# ramanSpectrometer_electronic_controlBoar.net
KiCad netlist of a schematic drawn in EAGLE
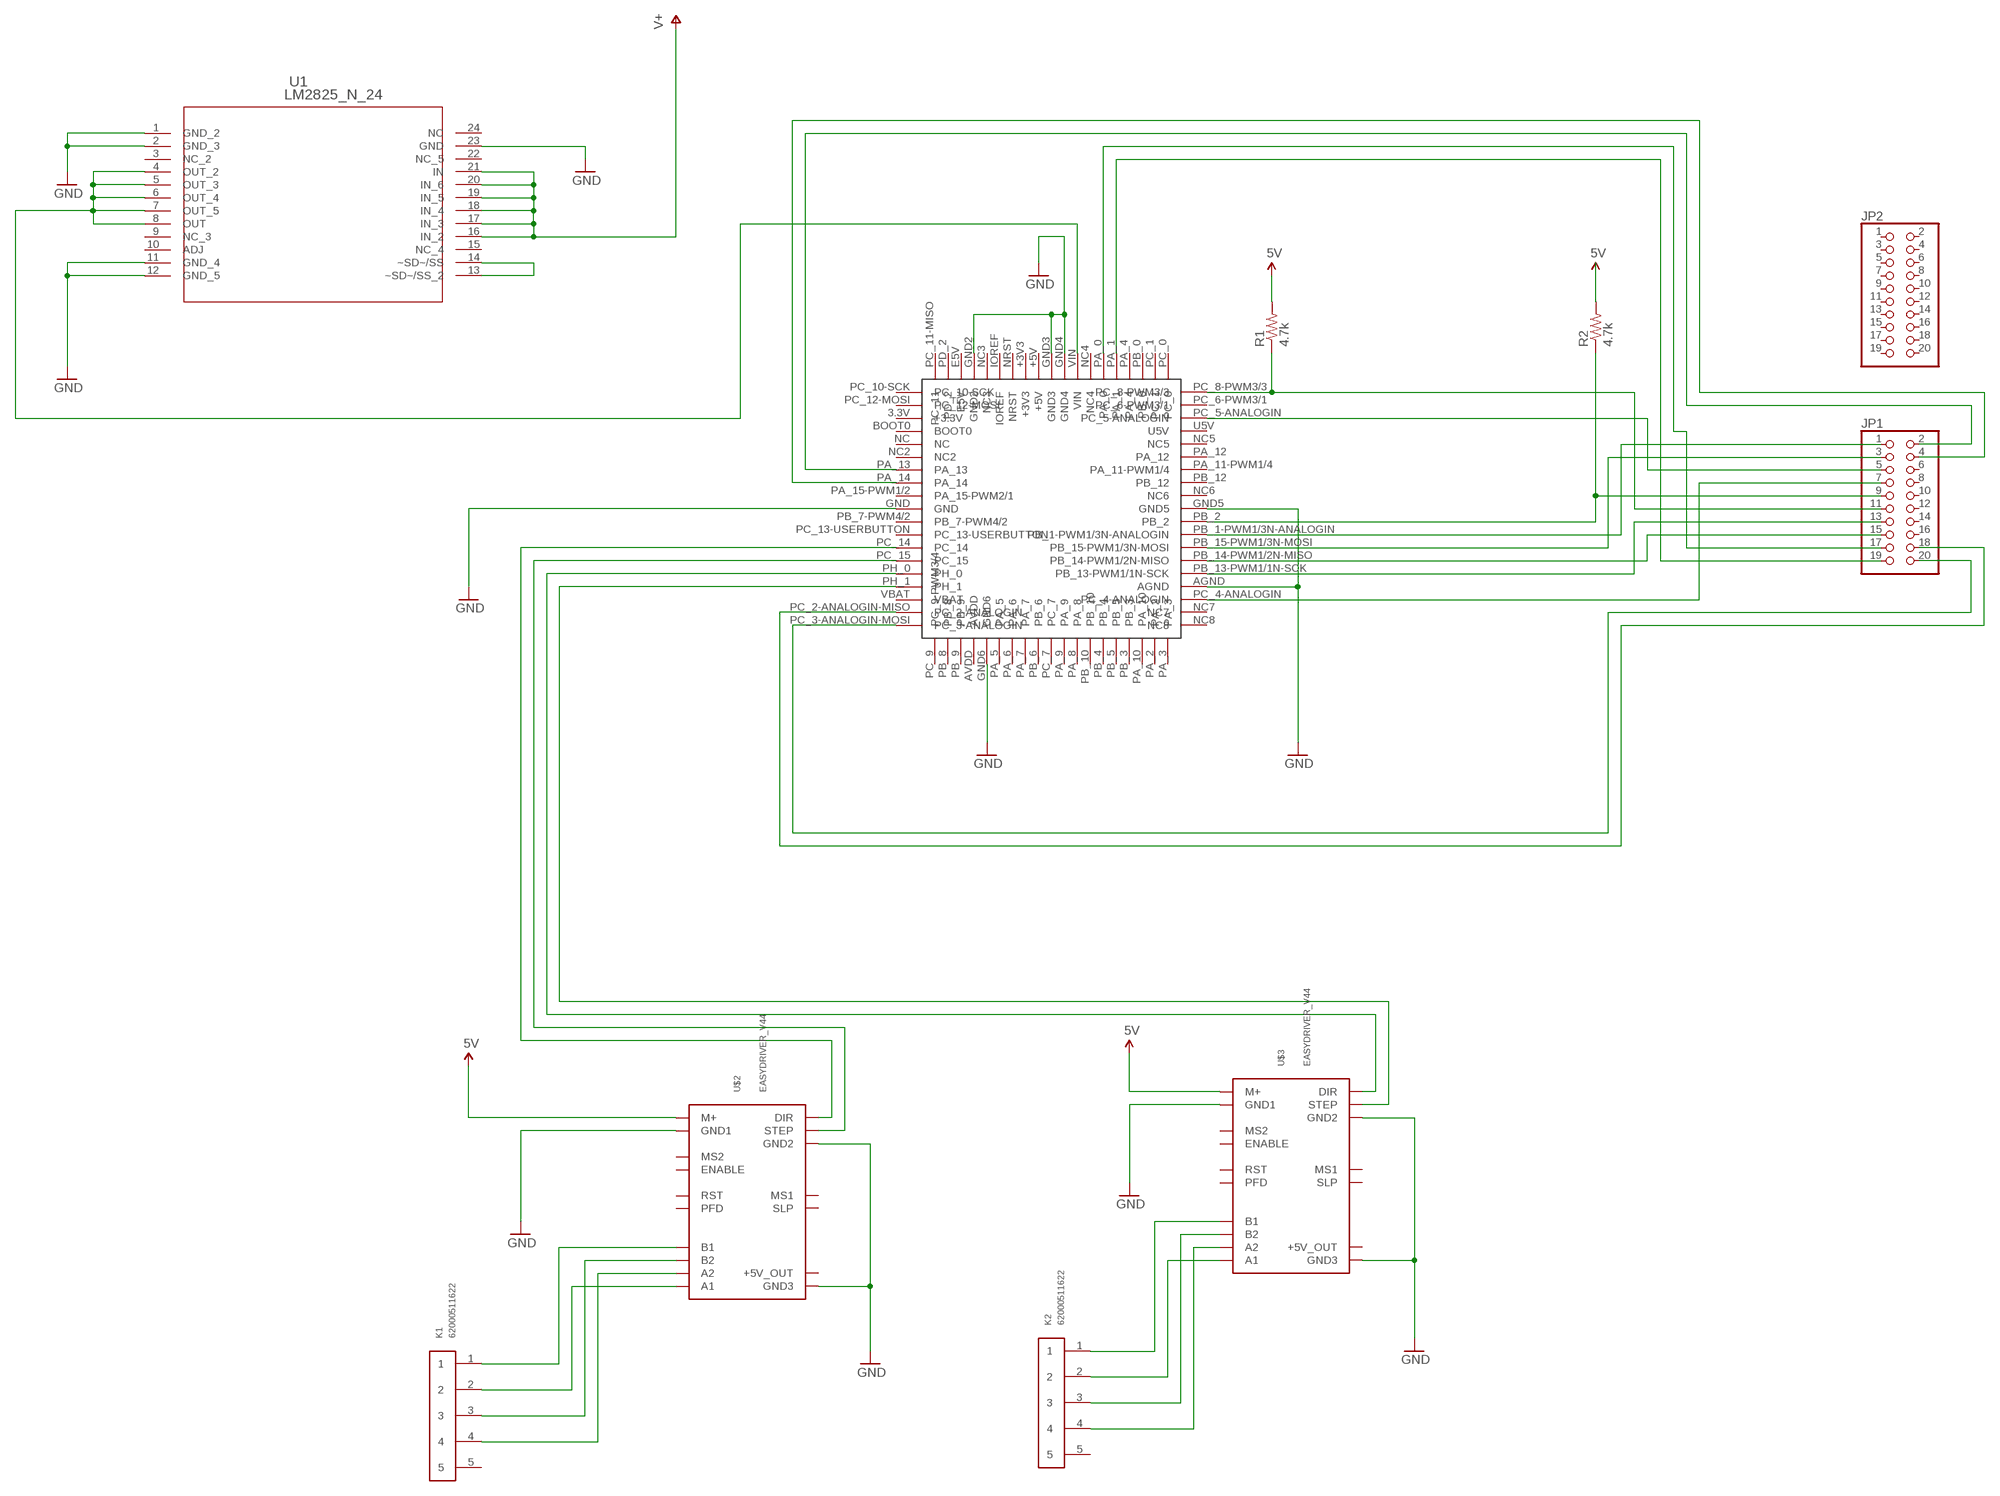
[diagram p0: schematic, sheet 1]

(export (version "E")
  (design (tool "Eeschema 10.0.6"))
  (components
    (comp (ref "JP1")
      (value "PINHD-2X10")
      (footprint "eagle-import:2X10")
      (libsource (lib "eagle-import") (part "PINHD-2X10"))
    )
    (comp (ref "JP2")
      (value "PINHD-2X10")
      (footprint "eagle-import:2X10")
      (libsource (lib "eagle-import") (part "PINHD-2X10"))
    )
    (comp (ref "K1")
      (value "62000511622")
      (footprint "eagle-import:62000511622")
      (libsource (lib "eagle-import") (part "62000511622"))
    )
    (comp (ref "K2")
      (value "62000511622")
      (footprint "eagle-import:62000511622")
      (libsource (lib "eagle-import") (part "62000511622"))
    )
    (comp (ref "R1")
      (value "4.7k")
      (footprint "eagle-import:AXIAL-0.3-KIT")
      (libsource (lib "eagle-import") (part "RESISTORKIT"))
    )
    (comp (ref "R2")
      (value "4.7k")
      (footprint "eagle-import:AXIAL-0.3-KIT")
      (libsource (lib "eagle-import") (part "RESISTORKIT"))
    )
    (comp (ref "U$1")
      (value "STNUCLEOF401RE")
      (footprint "eagle-import:F401-RE")
      (libsource (lib "eagle-import") (part "STNUCLEOF401RE"))
    )
    (comp (ref "U$2")
      (value "EASYDRIVER_V44")
      (footprint "eagle-import:EASYDRIVER_V44")
      (libsource (lib "eagle-import") (part "EASYDRIVER_V44"))
    )
    (comp (ref "U$3")
      (value "EASYDRIVER_V44")
      (footprint "eagle-import:EASYDRIVER_V44")
      (libsource (lib "eagle-import") (part "EASYDRIVER_V44"))
    )
    (comp (ref "U1")
      (value "LM2825_N_24")
      (footprint "eagle-import:NA24F")
      (fields (field (name "PARTNUMBER") "LM2825HN-ADJ"))
      (libsource (lib "eagle-import") (part "LM2825_N_24"))
    )
  )
  (nets
    (net (code "1") (name "/+3.3V") (class "Default")
      (node (ref "U$1") (pin "3.3V") (pinfunction "+3.3V_3.3V") (pintype "power_in"))
    )
    (net (code "2") (name "/AVDD") (class "Default")
      (node (ref "U$1") (pin "AVDD") (pinfunction "AVDD_AVDD") (pintype "power_in"))
    )
    (net (code "3") (name "/E5V") (class "Default")
      (node (ref "U$1") (pin "E5V") (pinfunction "E5V_E5V") (pintype "power_in"))
    )
    (net (code "4") (name "/NC6") (class "Default")
      (node (ref "U$1") (pin "NC6") (pinfunction "NC6_NC6") (pintype "power_in"))
    )
    (net (code "5") (name "/VBAT") (class "Default")
      (node (ref "U$1") (pin "VBAT") (pinfunction "VBAT_VBAT") (pintype "power_in"))
    )
    (net (code "6") (name "5V") (class "Default")
      (node (ref "R1") (pin "P$2") (pinfunction "2_P$2") (pintype "passive"))
      (node (ref "R2") (pin "P$2") (pinfunction "2_P$2") (pintype "passive"))
      (node (ref "U$2") (pin "M+") (pinfunction "M+_M+") (pintype "bidirectional"))
      (node (ref "U$3") (pin "M+") (pinfunction "M+_M+") (pintype "bidirectional"))
    )
    (net (code "7") (name "GND") (class "Default")
      (node (ref "U$1") (pin "AGND") (pinfunction "AGND_AGND") (pintype "power_in"))
      (node (ref "U$1") (pin "GND") (pinfunction "GND_GND") (pintype "power_in"))
      (node (ref "U$1") (pin "GND2") (pinfunction "GND2_GND2") (pintype "power_in"))
      (node (ref "U$1") (pin "GND3") (pinfunction "GND3_GND3") (pintype "bidirectional"))
      (node (ref "U$1") (pin "GND4") (pinfunction "GND4_GND4") (pintype "bidirectional"))
      (node (ref "U$1") (pin "GND5") (pinfunction "GND5_GND5") (pintype "bidirectional"))
      (node (ref "U$1") (pin "GND6") (pinfunction "GND6_GND6") (pintype "bidirectional"))
      (node (ref "U$2") (pin "GND1") (pinfunction "GND1_GND1") (pintype "bidirectional"))
      (node (ref "U$2") (pin "GND2") (pinfunction "GND2_GND2") (pintype "bidirectional"))
      (node (ref "U$2") (pin "GND3") (pinfunction "GND3_GND3") (pintype "bidirectional"))
      (node (ref "U$3") (pin "GND1") (pinfunction "GND1_GND1") (pintype "bidirectional"))
      (node (ref "U$3") (pin "GND2") (pinfunction "GND2_GND2") (pintype "bidirectional"))
      (node (ref "U$3") (pin "GND3") (pinfunction "GND3_GND3") (pintype "bidirectional"))
      (node (ref "U1") (pin "1") (pinfunction "GND_2_1") (pintype "passive"))
      (node (ref "U1") (pin "11") (pinfunction "GND_4_11") (pintype "passive"))
      (node (ref "U1") (pin "12") (pinfunction "GND_5_12") (pintype "passive"))
      (node (ref "U1") (pin "2") (pinfunction "GND_3_2") (pintype "passive"))
      (node (ref "U1") (pin "23") (pinfunction "GND_23") (pintype "passive"))
    )
    (net (code "8") (name "Net-(JP1-Pad1)") (class "Default")
      (node (ref "JP1") (pin "1") (pinfunction "1_1") (pintype "passive"))
      (node (ref "U$1") (pin "PB_1-PWM1/3N-ANALOGIN") (pinfunction "PB_1-PWM1/3N-ANALOGIN_PB_1-PWM1/3N-ANALOGIN") (pintype "bidirectional"))
    )
    (net (code "9") (name "Net-(JP1-Pad2)") (class "Default")
      (node (ref "JP1") (pin "2") (pinfunction "2_2") (pintype "passive"))
      (node (ref "U$1") (pin "PA_13") (pinfunction "PA_13_PA_13") (pintype "bidirectional"))
    )
    (net (code "10") (name "Net-(JP1-Pad3)") (class "Default")
      (node (ref "JP1") (pin "3") (pinfunction "3_3") (pintype "passive"))
      (node (ref "U$1") (pin "PB_15-PWM1/3N-MOSI") (pinfunction "PB_15-PWM1/3N-MOSI_PB_15-PWM1/3N-MOSI") (pintype "bidirectional"))
    )
    (net (code "11") (name "Net-(JP1-Pad4)") (class "Default")
      (node (ref "JP1") (pin "4") (pinfunction "4_4") (pintype "passive"))
      (node (ref "U$1") (pin "PA_14") (pinfunction "PA_14_PA_14") (pintype "bidirectional"))
    )
    (net (code "12") (name "Net-(JP1-Pad5)") (class "Default")
      (node (ref "JP1") (pin "5") (pinfunction "5_5") (pintype "passive"))
      (node (ref "U$1") (pin "PC_5-ANALOGIN") (pinfunction "PC_5-ANALOGIN_PC_5-ANALOGIN") (pintype "bidirectional"))
    )
    (net (code "13") (name "Net-(JP1-Pad7)") (class "Default")
      (node (ref "JP1") (pin "7") (pinfunction "7_7") (pintype "passive"))
      (node (ref "U$1") (pin "PC_4-ANALOGIN") (pinfunction "PC_4-ANALOGIN_PC_4-ANALOGIN") (pintype "bidirectional"))
    )
    (net (code "14") (name "Net-(JP1-Pad13)") (class "Default")
      (node (ref "JP1") (pin "13") (pinfunction "13_13") (pintype "passive"))
      (node (ref "U$1") (pin "PB_13-PWM1/1N-SCK") (pinfunction "PB_13-PWM1/1N-SCK_PB_13-PWM1/1N-SCK") (pintype "bidirectional"))
    )
    (net (code "15") (name "Net-(JP1-Pad15)") (class "Default")
      (node (ref "JP1") (pin "15") (pinfunction "15_15") (pintype "passive"))
      (node (ref "U$1") (pin "PB_14-PWM1/2N-MISO") (pinfunction "PB_14-PWM1/2N-MISO_PB_14-PWM1/2N-MISO") (pintype "bidirectional"))
    )
    (net (code "16") (name "Net-(JP1-Pad17)") (class "Default")
      (node (ref "JP1") (pin "17") (pinfunction "17_17") (pintype "passive"))
      (node (ref "U$1") (pin "PA_0") (pinfunction "PA_0_PA_0") (pintype "bidirectional"))
    )
    (net (code "17") (name "Net-(JP1-Pad19)") (class "Default")
      (node (ref "JP1") (pin "19") (pinfunction "19_19") (pintype "passive"))
      (node (ref "U$1") (pin "PA_1") (pinfunction "PA_1_PA_1") (pintype "bidirectional"))
    )
    (net (code "18") (name "Net-(K1-Pad1)") (class "Default")
      (node (ref "K1") (pin "1") (pinfunction "1_1") (pintype "bidirectional"))
      (node (ref "U$2") (pin "B1") (pinfunction "B1_B1") (pintype "bidirectional"))
    )
    (net (code "19") (name "Net-(K1-Pad2)") (class "Default")
      (node (ref "K1") (pin "2") (pinfunction "2_2") (pintype "bidirectional"))
      (node (ref "U$2") (pin "A1") (pinfunction "A1_A1") (pintype "bidirectional"))
    )
    (net (code "20") (name "Net-(K1-Pad3)") (class "Default")
      (node (ref "K1") (pin "3") (pinfunction "3_3") (pintype "bidirectional"))
      (node (ref "U$2") (pin "B2") (pinfunction "B2_B2") (pintype "bidirectional"))
    )
    (net (code "21") (name "Net-(K1-Pad4)") (class "Default")
      (node (ref "K1") (pin "4") (pinfunction "4_4") (pintype "bidirectional"))
      (node (ref "U$2") (pin "A2") (pinfunction "A2_A2") (pintype "bidirectional"))
    )
    (net (code "22") (name "Net-(K2-Pad1)") (class "Default")
      (node (ref "K2") (pin "1") (pinfunction "1_1") (pintype "bidirectional"))
      (node (ref "U$3") (pin "B1") (pinfunction "B1_B1") (pintype "bidirectional"))
    )
    (net (code "23") (name "Net-(K2-Pad2)") (class "Default")
      (node (ref "K2") (pin "2") (pinfunction "2_2") (pintype "bidirectional"))
      (node (ref "U$3") (pin "A1") (pinfunction "A1_A1") (pintype "bidirectional"))
    )
    (net (code "24") (name "Net-(K2-Pad3)") (class "Default")
      (node (ref "K2") (pin "3") (pinfunction "3_3") (pintype "bidirectional"))
      (node (ref "U$3") (pin "B2") (pinfunction "B2_B2") (pintype "bidirectional"))
    )
    (net (code "25") (name "Net-(K2-Pad4)") (class "Default")
      (node (ref "K2") (pin "4") (pinfunction "4_4") (pintype "bidirectional"))
      (node (ref "U$3") (pin "A2") (pinfunction "A2_A2") (pintype "bidirectional"))
    )
    (net (code "26") (name "Net-(R1-1)") (class "Default")
      (node (ref "JP1") (pin "11") (pinfunction "11_11") (pintype "passive"))
      (node (ref "R1") (pin "P$1") (pinfunction "1_P$1") (pintype "passive"))
      (node (ref "U$1") (pin "PC_8-PWM3/3") (pinfunction "PC_8-PWM3/3_PC_8-PWM3/3") (pintype "bidirectional"))
    )
    (net (code "27") (name "Net-(R2-1)") (class "Default")
      (node (ref "JP1") (pin "9") (pinfunction "9_9") (pintype "passive"))
      (node (ref "R2") (pin "P$1") (pinfunction "1_P$1") (pintype "passive"))
      (node (ref "U$1") (pin "PB_2") (pinfunction "PB_2_PB_2") (pintype "bidirectional"))
    )
    (net (code "28") (name "Net-(U$1-PC_2-ANALOGIN)") (class "Default")
      (node (ref "JP1") (pin "18") (pinfunction "18_18") (pintype "passive"))
      (node (ref "U$1") (pin "PC_2-ANALOGIN-MISO") (pinfunction "PC_2-ANALOGIN_PC_2-ANALOGIN-MISO") (pintype "bidirectional"))
    )
    (net (code "29") (name "Net-(U$1-PC_3-ANALOGIN)") (class "Default")
      (node (ref "JP1") (pin "20") (pinfunction "20_20") (pintype "passive"))
      (node (ref "U$1") (pin "PC_3-ANALOGIN-MOSI") (pinfunction "PC_3-ANALOGIN_PC_3-ANALOGIN-MOSI") (pintype "bidirectional"))
    )
    (net (code "30") (name "Net-(U$1-PadPC_14)") (class "Default")
      (node (ref "U$1") (pin "PC_14") (pinfunction "PC_14_PC_14") (pintype "bidirectional"))
      (node (ref "U$2") (pin "DIR") (pinfunction "DIR_DIR") (pintype "bidirectional"))
    )
    (net (code "31") (name "Net-(U$1-PadPC_15)") (class "Default")
      (node (ref "U$1") (pin "PC_15") (pinfunction "PC_15_PC_15") (pintype "bidirectional"))
      (node (ref "U$2") (pin "STEP") (pinfunction "STEP_STEP") (pintype "bidirectional"))
    )
    (net (code "32") (name "Net-(U$1-PadPH_0)") (class "Default")
      (node (ref "U$1") (pin "PH_0") (pinfunction "PH_0_PH_0") (pintype "bidirectional"))
      (node (ref "U$3") (pin "DIR") (pinfunction "DIR_DIR") (pintype "bidirectional"))
    )
    (net (code "33") (name "Net-(U$1-PadPH_1)") (class "Default")
      (node (ref "U$1") (pin "PH_1") (pinfunction "PH_1_PH_1") (pintype "bidirectional"))
      (node (ref "U$3") (pin "STEP") (pinfunction "STEP_STEP") (pintype "bidirectional"))
    )
    (net (code "34") (name "Net-(U1-OUT)") (class "Default")
      (node (ref "U$1") (pin "VIN") (pinfunction "VIN_VIN") (pintype "bidirectional"))
      (node (ref "U1") (pin "4") (pinfunction "OUT_2_4") (pintype "output"))
      (node (ref "U1") (pin "5") (pinfunction "OUT_3_5") (pintype "output"))
      (node (ref "U1") (pin "6") (pinfunction "OUT_4_6") (pintype "output"))
      (node (ref "U1") (pin "7") (pinfunction "OUT_5_7") (pintype "output"))
      (node (ref "U1") (pin "8") (pinfunction "OUT_8") (pintype "output"))
    )
    (net (code "35") (name "Net-(U1-~{SD}{slash}SS)") (class "Default")
      (node (ref "U1") (pin "13") (pinfunction "~{SD}/SS_2_13") (pintype "passive"))
      (node (ref "U1") (pin "14") (pinfunction "~{SD}/SS_14") (pintype "passive"))
    )
    (net (code "36") (name "V+") (class "Default")
      (node (ref "U1") (pin "16") (pinfunction "IN_2_16") (pintype "input"))
      (node (ref "U1") (pin "17") (pinfunction "IN_3_17") (pintype "input"))
      (node (ref "U1") (pin "18") (pinfunction "IN_4_18") (pintype "input"))
      (node (ref "U1") (pin "19") (pinfunction "IN_5_19") (pintype "input"))
      (node (ref "U1") (pin "20") (pinfunction "IN_6_20") (pintype "input"))
      (node (ref "U1") (pin "21") (pinfunction "IN_21") (pintype "input"))
    )
    (net (code "37") (name "unconnected-(JP1-Pad6)") (class "Default")
      (node (ref "JP1") (pin "6") (pinfunction "6_6") (pintype "passive"))
    )
    (net (code "38") (name "unconnected-(JP1-Pad8)") (class "Default")
      (node (ref "JP1") (pin "8") (pinfunction "8_8") (pintype "passive"))
    )
    (net (code "39") (name "unconnected-(JP1-Pad10)") (class "Default")
      (node (ref "JP1") (pin "10") (pinfunction "10_10") (pintype "passive"))
    )
    (net (code "40") (name "unconnected-(JP1-Pad12)") (class "Default")
      (node (ref "JP1") (pin "12") (pinfunction "12_12") (pintype "passive"))
    )
    (net (code "41") (name "unconnected-(JP1-Pad14)") (class "Default")
      (node (ref "JP1") (pin "14") (pinfunction "14_14") (pintype "passive"))
    )
    (net (code "42") (name "unconnected-(JP1-Pad16)") (class "Default")
      (node (ref "JP1") (pin "16") (pinfunction "16_16") (pintype "passive"))
    )
    (net (code "43") (name "unconnected-(JP2-Pad1)") (class "Default")
      (node (ref "JP2") (pin "1") (pinfunction "1_1") (pintype "passive"))
    )
    (net (code "44") (name "unconnected-(JP2-Pad2)") (class "Default")
      (node (ref "JP2") (pin "2") (pinfunction "2_2") (pintype "passive"))
    )
    (net (code "45") (name "unconnected-(JP2-Pad3)") (class "Default")
      (node (ref "JP2") (pin "3") (pinfunction "3_3") (pintype "passive"))
    )
    (net (code "46") (name "unconnected-(JP2-Pad4)") (class "Default")
      (node (ref "JP2") (pin "4") (pinfunction "4_4") (pintype "passive"))
    )
    (net (code "47") (name "unconnected-(JP2-Pad5)") (class "Default")
      (node (ref "JP2") (pin "5") (pinfunction "5_5") (pintype "passive"))
    )
    (net (code "48") (name "unconnected-(JP2-Pad6)") (class "Default")
      (node (ref "JP2") (pin "6") (pinfunction "6_6") (pintype "passive"))
    )
    (net (code "49") (name "unconnected-(JP2-Pad7)") (class "Default")
      (node (ref "JP2") (pin "7") (pinfunction "7_7") (pintype "passive"))
    )
    (net (code "50") (name "unconnected-(JP2-Pad8)") (class "Default")
      (node (ref "JP2") (pin "8") (pinfunction "8_8") (pintype "passive"))
    )
    (net (code "51") (name "unconnected-(JP2-Pad9)") (class "Default")
      (node (ref "JP2") (pin "9") (pinfunction "9_9") (pintype "passive"))
    )
    (net (code "52") (name "unconnected-(JP2-Pad10)") (class "Default")
      (node (ref "JP2") (pin "10") (pinfunction "10_10") (pintype "passive"))
    )
    (net (code "53") (name "unconnected-(JP2-Pad11)") (class "Default")
      (node (ref "JP2") (pin "11") (pinfunction "11_11") (pintype "passive"))
    )
    (net (code "54") (name "unconnected-(JP2-Pad12)") (class "Default")
      (node (ref "JP2") (pin "12") (pinfunction "12_12") (pintype "passive"))
    )
    (net (code "55") (name "unconnected-(JP2-Pad13)") (class "Default")
      (node (ref "JP2") (pin "13") (pinfunction "13_13") (pintype "passive"))
    )
    (net (code "56") (name "unconnected-(JP2-Pad14)") (class "Default")
      (node (ref "JP2") (pin "14") (pinfunction "14_14") (pintype "passive"))
    )
    (net (code "57") (name "unconnected-(JP2-Pad15)") (class "Default")
      (node (ref "JP2") (pin "15") (pinfunction "15_15") (pintype "passive"))
    )
    (net (code "58") (name "unconnected-(JP2-Pad16)") (class "Default")
      (node (ref "JP2") (pin "16") (pinfunction "16_16") (pintype "passive"))
    )
    (net (code "59") (name "unconnected-(JP2-Pad17)") (class "Default")
      (node (ref "JP2") (pin "17") (pinfunction "17_17") (pintype "passive"))
    )
    (net (code "60") (name "unconnected-(JP2-Pad18)") (class "Default")
      (node (ref "JP2") (pin "18") (pinfunction "18_18") (pintype "passive"))
    )
    (net (code "61") (name "unconnected-(JP2-Pad19)") (class "Default")
      (node (ref "JP2") (pin "19") (pinfunction "19_19") (pintype "passive"))
    )
    (net (code "62") (name "unconnected-(JP2-Pad20)") (class "Default")
      (node (ref "JP2") (pin "20") (pinfunction "20_20") (pintype "passive"))
    )
    (net (code "63") (name "unconnected-(K1-Pad5)") (class "Default")
      (node (ref "K1") (pin "5") (pinfunction "5_5") (pintype "bidirectional"))
    )
    (net (code "64") (name "unconnected-(K2-Pad5)") (class "Default")
      (node (ref "K2") (pin "5") (pinfunction "5_5") (pintype "bidirectional"))
    )
    (net (code "65") (name "unconnected-(U$1-PA_15-PWM2{slash}1-PadPA_15-PWM1{slash}2)") (class "Default")
      (node (ref "U$1") (pin "PA_15-PWM1/2") (pinfunction "PA_15-PWM2/1_PA_15-PWM1/2") (pintype "bidirectional"))
    )
    (net (code "66") (name "unconnected-(U$1-PC_9-PWM3{slash}4-PadPC_9)") (class "Default")
      (node (ref "U$1") (pin "PC_9") (pinfunction "PC_9-PWM3/4_PC_9") (pintype "bidirectional"))
    )
    (net (code "67") (name "unconnected-(U$1-PC_11-PadPC_11-MISO)") (class "Default")
      (node (ref "U$1") (pin "PC_11-MISO") (pinfunction "PC_11_PC_11-MISO") (pintype "bidirectional"))
    )
    (net (code "68") (name "unconnected-(U$1-Pad+3V3)") (class "Default")
      (node (ref "U$1") (pin "+3V3") (pinfunction "+3V3_+3V3") (pintype "bidirectional"))
    )
    (net (code "69") (name "unconnected-(U$1-Pad+5V)") (class "Default")
      (node (ref "U$1") (pin "+5V") (pinfunction "+5V_+5V") (pintype "bidirectional"))
    )
    (net (code "70") (name "unconnected-(U$1-PadBOOT0)") (class "Default")
      (node (ref "U$1") (pin "BOOT0") (pinfunction "BOOT0_BOOT0") (pintype "bidirectional"))
    )
    (net (code "71") (name "unconnected-(U$1-PadIOREF)") (class "Default")
      (node (ref "U$1") (pin "IOREF") (pinfunction "IOREF_IOREF") (pintype "bidirectional"))
    )
    (net (code "72") (name "unconnected-(U$1-PadNC)") (class "Default")
      (node (ref "U$1") (pin "NC") (pinfunction "NC_NC") (pintype "no_connect"))
    )
    (net (code "73") (name "unconnected-(U$1-PadNC2)") (class "Default")
      (node (ref "U$1") (pin "NC2") (pinfunction "NC2_NC2") (pintype "no_connect"))
    )
    (net (code "74") (name "unconnected-(U$1-PadNC3)") (class "Default")
      (node (ref "U$1") (pin "NC3") (pinfunction "NC3_NC3") (pintype "no_connect"))
    )
    (net (code "75") (name "unconnected-(U$1-PadNC4)") (class "Default")
      (node (ref "U$1") (pin "NC4") (pinfunction "NC4_NC4") (pintype "bidirectional"))
    )
    (net (code "76") (name "unconnected-(U$1-PadNC5)") (class "Default")
      (node (ref "U$1") (pin "NC5") (pinfunction "NC5_NC5") (pintype "bidirectional"))
    )
    (net (code "77") (name "unconnected-(U$1-PadNC7)") (class "Default")
      (node (ref "U$1") (pin "NC7") (pinfunction "NC7_NC7") (pintype "bidirectional"))
    )
    (net (code "78") (name "unconnected-(U$1-PadNC8)") (class "Default")
      (node (ref "U$1") (pin "NC8") (pinfunction "NC8_NC8") (pintype "bidirectional"))
    )
    (net (code "79") (name "unconnected-(U$1-PadNRST)") (class "Default")
      (node (ref "U$1") (pin "NRST") (pinfunction "NRST_NRST") (pintype "bidirectional"))
    )
    (net (code "80") (name "unconnected-(U$1-PadPA_2)") (class "Default")
      (node (ref "U$1") (pin "PA_2") (pinfunction "PA_2_PA_2") (pintype "bidirectional"))
    )
    (net (code "81") (name "unconnected-(U$1-PadPA_3)") (class "Default")
      (node (ref "U$1") (pin "PA_3") (pinfunction "PA_3_PA_3") (pintype "bidirectional"))
    )
    (net (code "82") (name "unconnected-(U$1-PadPA_4)") (class "Default")
      (node (ref "U$1") (pin "PA_4") (pinfunction "PA_4_PA_4") (pintype "bidirectional"))
    )
    (net (code "83") (name "unconnected-(U$1-PadPA_5)") (class "Default")
      (node (ref "U$1") (pin "PA_5") (pinfunction "PA_5_PA_5") (pintype "bidirectional"))
    )
    (net (code "84") (name "unconnected-(U$1-PadPA_6)") (class "Default")
      (node (ref "U$1") (pin "PA_6") (pinfunction "PA_6_PA_6") (pintype "bidirectional"))
    )
    (net (code "85") (name "unconnected-(U$1-PadPA_7)") (class "Default")
      (node (ref "U$1") (pin "PA_7") (pinfunction "PA_7_PA_7") (pintype "bidirectional"))
    )
    (net (code "86") (name "unconnected-(U$1-PadPA_8)") (class "Default")
      (node (ref "U$1") (pin "PA_8") (pinfunction "PA_8_PA_8") (pintype "bidirectional"))
    )
    (net (code "87") (name "unconnected-(U$1-PadPA_9)") (class "Default")
      (node (ref "U$1") (pin "PA_9") (pinfunction "PA_9_PA_9") (pintype "bidirectional"))
    )
    (net (code "88") (name "unconnected-(U$1-PadPA_10)") (class "Default")
      (node (ref "U$1") (pin "PA_10") (pinfunction "PA_10_PA_10") (pintype "bidirectional"))
    )
    (net (code "89") (name "unconnected-(U$1-PadPA_11-PWM1{slash}4)") (class "Default")
      (node (ref "U$1") (pin "PA_11-PWM1/4") (pinfunction "PA_11-PWM1/4_PA_11-PWM1/4") (pintype "bidirectional"))
    )
    (net (code "90") (name "unconnected-(U$1-PadPA_12)") (class "Default")
      (node (ref "U$1") (pin "PA_12") (pinfunction "PA_12_PA_12") (pintype "bidirectional"))
    )
    (net (code "91") (name "unconnected-(U$1-PadPB_0)") (class "Default")
      (node (ref "U$1") (pin "PB_0") (pinfunction "PB_0_PB_0") (pintype "bidirectional"))
    )
    (net (code "92") (name "unconnected-(U$1-PadPB_3)") (class "Default")
      (node (ref "U$1") (pin "PB_3") (pinfunction "PB_3_PB_3") (pintype "bidirectional"))
    )
    (net (code "93") (name "unconnected-(U$1-PadPB_4)") (class "Default")
      (node (ref "U$1") (pin "PB_4") (pinfunction "PB_4_PB_4") (pintype "bidirectional"))
    )
    (net (code "94") (name "unconnected-(U$1-PadPB_5)") (class "Default")
      (node (ref "U$1") (pin "PB_5") (pinfunction "PB_5_PB_5") (pintype "bidirectional"))
    )
    (net (code "95") (name "unconnected-(U$1-PadPB_6)") (class "Default")
      (node (ref "U$1") (pin "PB_6") (pinfunction "PB_6_PB_6") (pintype "bidirectional"))
    )
    (net (code "96") (name "unconnected-(U$1-PadPB_7-PWM4{slash}2)") (class "Default")
      (node (ref "U$1") (pin "PB_7-PWM4/2") (pinfunction "PB_7-PWM4/2_PB_7-PWM4/2") (pintype "bidirectional"))
    )
    (net (code "97") (name "unconnected-(U$1-PadPB_8)") (class "Default")
      (node (ref "U$1") (pin "PB_8") (pinfunction "PB_8_PB_8") (pintype "bidirectional"))
    )
    (net (code "98") (name "unconnected-(U$1-PadPB_9)") (class "Default")
      (node (ref "U$1") (pin "PB_9") (pinfunction "PB_9_PB_9") (pintype "bidirectional"))
    )
    (net (code "99") (name "unconnected-(U$1-PadPB_10)") (class "Default")
      (node (ref "U$1") (pin "PB_10") (pinfunction "PB_10_PB_10") (pintype "bidirectional"))
    )
    (net (code "100") (name "unconnected-(U$1-PadPB_12)") (class "Default")
      (node (ref "U$1") (pin "PB_12") (pinfunction "PB_12_PB_12") (pintype "bidirectional"))
    )
    (net (code "101") (name "unconnected-(U$1-PadPC_0)") (class "Default")
      (node (ref "U$1") (pin "PC_0") (pinfunction "PC_0_PC_0") (pintype "bidirectional"))
    )
    (net (code "102") (name "unconnected-(U$1-PadPC_1)") (class "Default")
      (node (ref "U$1") (pin "PC_1") (pinfunction "PC_1_PC_1") (pintype "bidirectional"))
    )
    (net (code "103") (name "unconnected-(U$1-PadPC_6-PWM3{slash}1)") (class "Default")
      (node (ref "U$1") (pin "PC_6-PWM3/1") (pinfunction "PC_6-PWM3/1_PC_6-PWM3/1") (pintype "bidirectional"))
    )
    (net (code "104") (name "unconnected-(U$1-PadPC_7)") (class "Default")
      (node (ref "U$1") (pin "PC_7") (pinfunction "PC_7_PC_7") (pintype "bidirectional"))
    )
    (net (code "105") (name "unconnected-(U$1-PadPC_10-SCK)") (class "Default")
      (node (ref "U$1") (pin "PC_10-SCK") (pinfunction "PC_10-SCK_PC_10-SCK") (pintype "bidirectional"))
    )
    (net (code "106") (name "unconnected-(U$1-PadPC_12-MOSI)") (class "Default")
      (node (ref "U$1") (pin "PC_12-MOSI") (pinfunction "PC_12-MOSI_PC_12-MOSI") (pintype "bidirectional"))
    )
    (net (code "107") (name "unconnected-(U$1-PadPC_13-USERBUTTON)") (class "Default")
      (node (ref "U$1") (pin "PC_13-USERBUTTON") (pinfunction "PC_13-USERBUTTON_PC_13-USERBUTTON") (pintype "bidirectional"))
    )
    (net (code "108") (name "unconnected-(U$1-PadPD_2)") (class "Default")
      (node (ref "U$1") (pin "PD_2") (pinfunction "PD_2_PD_2") (pintype "bidirectional"))
    )
    (net (code "109") (name "unconnected-(U$1-PadU5V)") (class "Default")
      (node (ref "U$1") (pin "U5V") (pinfunction "U5V_U5V") (pintype "bidirectional"))
    )
    (net (code "110") (name "unconnected-(U$2-+5V_OUT-PadP$11)") (class "Default")
      (node (ref "U$2") (pin "P$11") (pinfunction "+5V_OUT_P$11") (pintype "bidirectional"))
    )
    (net (code "111") (name "unconnected-(U$2-PadENABLE)") (class "Default")
      (node (ref "U$2") (pin "ENABLE") (pinfunction "ENABLE_ENABLE") (pintype "bidirectional"))
    )
    (net (code "112") (name "unconnected-(U$2-PadMS1)") (class "Default")
      (node (ref "U$2") (pin "MS1") (pinfunction "MS1_MS1") (pintype "bidirectional"))
    )
    (net (code "113") (name "unconnected-(U$2-PadMS2)") (class "Default")
      (node (ref "U$2") (pin "MS2") (pinfunction "MS2_MS2") (pintype "bidirectional"))
    )
    (net (code "114") (name "unconnected-(U$2-PadPFD)") (class "Default")
      (node (ref "U$2") (pin "PFD") (pinfunction "PFD_PFD") (pintype "bidirectional"))
    )
    (net (code "115") (name "unconnected-(U$2-PadRST)") (class "Default")
      (node (ref "U$2") (pin "RST") (pinfunction "RST_RST") (pintype "bidirectional"))
    )
    (net (code "116") (name "unconnected-(U$2-SLP-PadSLEEP)") (class "Default")
      (node (ref "U$2") (pin "SLEEP") (pinfunction "SLP_SLEEP") (pintype "bidirectional"))
    )
    (net (code "117") (name "unconnected-(U$3-+5V_OUT-PadP$11)") (class "Default")
      (node (ref "U$3") (pin "P$11") (pinfunction "+5V_OUT_P$11") (pintype "bidirectional"))
    )
    (net (code "118") (name "unconnected-(U$3-PadENABLE)") (class "Default")
      (node (ref "U$3") (pin "ENABLE") (pinfunction "ENABLE_ENABLE") (pintype "bidirectional"))
    )
    (net (code "119") (name "unconnected-(U$3-PadMS1)") (class "Default")
      (node (ref "U$3") (pin "MS1") (pinfunction "MS1_MS1") (pintype "bidirectional"))
    )
    (net (code "120") (name "unconnected-(U$3-PadMS2)") (class "Default")
      (node (ref "U$3") (pin "MS2") (pinfunction "MS2_MS2") (pintype "bidirectional"))
    )
    (net (code "121") (name "unconnected-(U$3-PadPFD)") (class "Default")
      (node (ref "U$3") (pin "PFD") (pinfunction "PFD_PFD") (pintype "bidirectional"))
    )
    (net (code "122") (name "unconnected-(U$3-PadRST)") (class "Default")
      (node (ref "U$3") (pin "RST") (pinfunction "RST_RST") (pintype "bidirectional"))
    )
    (net (code "123") (name "unconnected-(U$3-SLP-PadSLEEP)") (class "Default")
      (node (ref "U$3") (pin "SLEEP") (pinfunction "SLP_SLEEP") (pintype "bidirectional"))
    )
    (net (code "124") (name "unconnected-(U1-ADJ-Pad10)") (class "Default")
      (node (ref "U1") (pin "10") (pinfunction "ADJ_10") (pintype "passive"))
    )
    (net (code "125") (name "unconnected-(U1-NC-Pad24)") (class "Default")
      (node (ref "U1") (pin "24") (pinfunction "NC_24") (pintype "passive"))
    )
    (net (code "126") (name "unconnected-(U1-NC_2-Pad3)") (class "Default")
      (node (ref "U1") (pin "3") (pinfunction "NC_2_3") (pintype "passive"))
    )
    (net (code "127") (name "unconnected-(U1-NC_3-Pad9)") (class "Default")
      (node (ref "U1") (pin "9") (pinfunction "NC_3_9") (pintype "passive"))
    )
    (net (code "128") (name "unconnected-(U1-NC_4-Pad15)") (class "Default")
      (node (ref "U1") (pin "15") (pinfunction "NC_4_15") (pintype "passive"))
    )
    (net (code "129") (name "unconnected-(U1-NC_5-Pad22)") (class "Default")
      (node (ref "U1") (pin "22") (pinfunction "NC_5_22") (pintype "passive"))
    )
  )
)
